# i2c_video_clock.net
KiCad netlist of a schematic drawn in Altium Designer
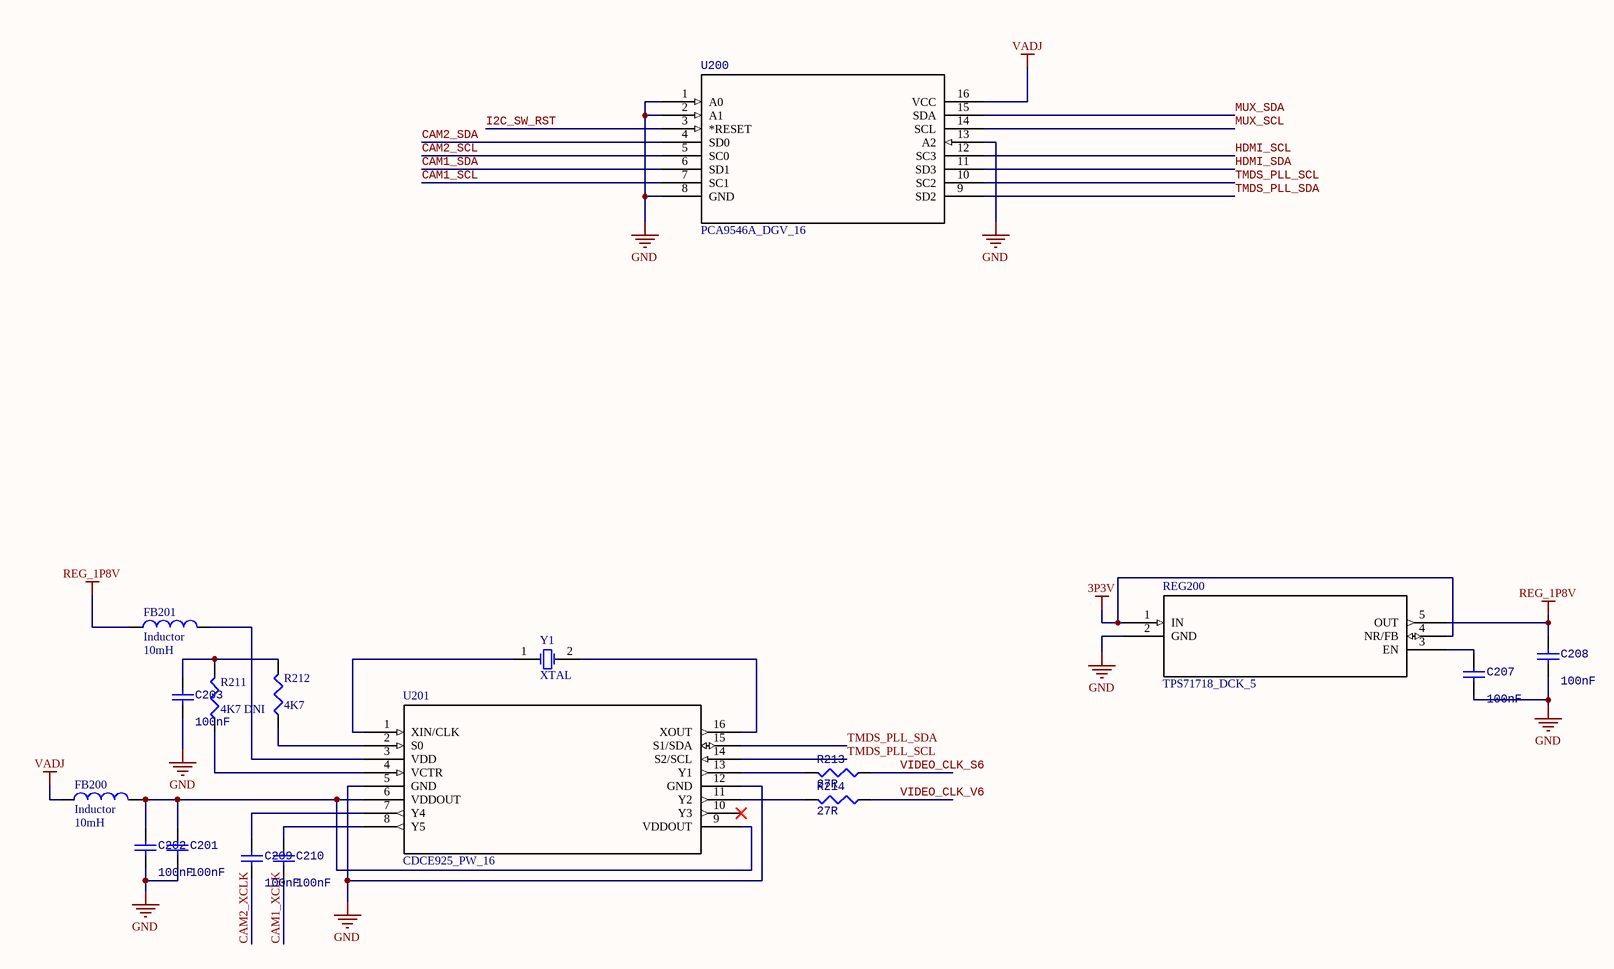
[diagram p0: i2c_video_clock.SchDoc]

(export (version "E")
  (design (tool "Eeschema 10.0.6"))
  (components
    (comp (ref "C201")
      (value "100nF")
      (footprint "1608[0603]")
      (description "Capacitor (Semiconductor SIM Model)")
      (fields (field (name "Comment") "Cap") (field (name "PUBLISHER") "Altium Limited"))
      (libsource (lib "Miscellaneous Devices") (part "Cap Semi"))
    )
    (comp (ref "C202")
      (value "100nF")
      (footprint "1608[0603]")
      (description "Capacitor (Semiconductor SIM Model)")
      (fields (field (name "Comment") "Cap") (field (name "PUBLISHER") "Altium Limited"))
      (libsource (lib "Miscellaneous Devices") (part "Cap Semi"))
    )
    (comp (ref "C203")
      (value "100nF")
      (footprint "1608[0603]")
      (description "Capacitor (Semiconductor SIM Model)")
      (fields (field (name "Comment") "Cap") (field (name "PUBLISHER") "Altium Limited"))
      (libsource (lib "Miscellaneous Devices") (part "Cap Semi"))
    )
    (comp (ref "C207")
      (value "100nF")
      (footprint "1608[0603]")
      (description "Capacitor (Semiconductor SIM Model)")
      (fields (field (name "Comment") "Cap") (field (name "PUBLISHER") "Altium Limited"))
      (libsource (lib "Miscellaneous Devices") (part "Cap Semi"))
    )
    (comp (ref "C208")
      (value "100nF")
      (footprint "1608[0603]")
      (description "Capacitor (Semiconductor SIM Model)")
      (fields (field (name "Comment") "Cap") (field (name "PUBLISHER") "Altium Limited"))
      (libsource (lib "Miscellaneous Devices") (part "Cap Semi"))
    )
    (comp (ref "C209")
      (value "100nF")
      (footprint "1608[0603]")
      (description "Capacitor (Semiconductor SIM Model)")
      (fields (field (name "Comment") "Cap") (field (name "PUBLISHER") "Altium Limited"))
      (libsource (lib "Miscellaneous Devices") (part "Cap Semi"))
    )
    (comp (ref "C210")
      (value "100nF")
      (footprint "1608[0603]")
      (description "Capacitor (Semiconductor SIM Model)")
      (fields (field (name "Comment") "Cap") (field (name "PUBLISHER") "Altium Limited"))
      (libsource (lib "Miscellaneous Devices") (part "Cap Semi"))
    )
    (comp (ref "FB200")
      (value "Inductor")
      (footprint "0603")
      (fields (field (name "ALTIUM_VALUE") "10mH") (field (name "PUBLISHER") "Altium Limited"))
      (libsource (lib "Miscellaneous Devices") (part "Inductor"))
    )
    (comp (ref "FB201")
      (value "Inductor")
      (footprint "0603")
      (fields (field (name "ALTIUM_VALUE") "10mH") (field (name "PUBLISHER") "Altium Limited"))
      (libsource (lib "Miscellaneous Devices") (part "Inductor"))
    )
    (comp (ref "R211")
      (value "4K7 DNI")
      (footprint "J1-0603")
      (description "Resistor")
      (fields (field (name "Comment") "Res3") (field (name "PUBLISHER") "Altium Limited"))
      (libsource (lib "Miscellaneous Devices") (part "Res3"))
    )
    (comp (ref "R212")
      (value "4K7")
      (footprint "J1-0603")
      (description "Resistor")
      (fields (field (name "Comment") "Res3") (field (name "PUBLISHER") "Altium Limited"))
      (libsource (lib "Miscellaneous Devices") (part "Res3"))
    )
    (comp (ref "R213")
      (value "27R")
      (footprint "J1-0603")
      (description "Resistor")
      (fields (field (name "Comment") "Res3") (field (name "PUBLISHER") "Altium Limited"))
      (libsource (lib "Miscellaneous Devices") (part "Res3"))
    )
    (comp (ref "R214")
      (value "27R")
      (footprint "J1-0603")
      (description "Resistor")
      (fields (field (name "Comment") "Res3") (field (name "PUBLISHER") "Altium Limited"))
      (libsource (lib "Miscellaneous Devices") (part "Res3"))
    )
    (comp (ref "REG200")
      (value "TPS71718_DCK_5")
      (footprint "DCK5")
      (description "Imported")
      (fields
        (field (name "MANUFACTURER_PART_NUMBER") "tps71718_dck_5")
        (field (name "GENERIC_PART_NUMBER") "TPS71718")
      )
      (libsource (lib "TPS71718DCK") (part "TPS71718_DCK_5"))
    )
    (comp (ref "U200")
      (value "PCA9546A_DGV_16")
      (footprint "DGV16")
      (description "Imported")
      (fields
        (field (name "MANUFACTURER") "Texas Instruments")
        (field (name "GENERIC_PART_NUMBER") "PCA9546A")
      )
      (libsource (lib "PCA9546ADGV") (part "PCA9546A_DGV_16"))
    )
    (comp (ref "U201")
      (value "CDCE925_PW_16")
      (footprint "PW16")
      (description "Imported")
      (fields
        (field (name "MANUFACTURER") "Texas Instruments")
        (field (name "GENERIC_PART_NUMBER") "CDCE925")
      )
      (libsource (lib "CDCE925PW") (part "CDCE925_PW_16"))
    )
    (comp (ref "Y1")
      (value "XTAL")
      (footprint "R38")
      (description "Crystal Oscillator")
      (fields (field (name "PUBLISHER") "Altium Limited"))
      (libsource (lib "Miscellaneous Devices") (part "XTAL"))
    )
  )
  (nets
    (net (code "1") (name "/CAM1_SCL") (class "Default")
      (node (ref "U200") (pin "7") (pinfunction "SC1_7") (pintype "passive"))
    )
    (net (code "2") (name "/CAM1_SDA") (class "Default")
      (node (ref "U200") (pin "6") (pinfunction "SD1_6") (pintype "passive"))
    )
    (net (code "3") (name "/CAM1_XCLK") (class "Default")
      (node (ref "C210") (pin "1") (pinfunction "1_1") (pintype "passive"))
    )
    (net (code "4") (name "/CAM2_SCL") (class "Default")
      (node (ref "U200") (pin "5") (pinfunction "SC0_5") (pintype "passive"))
    )
    (net (code "5") (name "/CAM2_SDA") (class "Default")
      (node (ref "U200") (pin "4") (pinfunction "SD0_4") (pintype "passive"))
    )
    (net (code "6") (name "/CAM2_XCLK") (class "Default")
      (node (ref "C209") (pin "1") (pinfunction "1_1") (pintype "passive"))
    )
    (net (code "7") (name "/HDMI_SCL") (class "Default")
      (node (ref "U200") (pin "12") (pinfunction "SC3_12") (pintype "passive"))
    )
    (net (code "8") (name "/HDMI_SDA") (class "Default")
      (node (ref "U200") (pin "11") (pinfunction "SD3_11") (pintype "passive"))
    )
    (net (code "9") (name "/I2C_SW_RST") (class "Default")
      (node (ref "U200") (pin "3") (pinfunction "*RESET_3") (pintype "input"))
    )
    (net (code "10") (name "/MUX_SCL") (class "Default")
      (node (ref "U200") (pin "14") (pinfunction "SCL_14") (pintype "passive"))
    )
    (net (code "11") (name "/MUX_SDA") (class "Default")
      (node (ref "U200") (pin "15") (pinfunction "SDA_15") (pintype "passive"))
    )
    (net (code "12") (name "/TMDS_PLL_SCL") (class "Default")
      (node (ref "U200") (pin "10") (pinfunction "SC2_10") (pintype "passive"))
      (node (ref "U201") (pin "14") (pinfunction "S2/SCL_14") (pintype "input"))
    )
    (net (code "13") (name "/TMDS_PLL_SDA") (class "Default")
      (node (ref "U200") (pin "9") (pinfunction "SD2_9") (pintype "passive"))
      (node (ref "U201") (pin "15") (pinfunction "S1/SDA_15") (pintype "bidirectional"))
    )
    (net (code "14") (name "/VIDEO_CLK_S6") (class "Default")
      (node (ref "R213") (pin "1") (pinfunction "1_1") (pintype "passive"))
    )
    (net (code "15") (name "/VIDEO_CLK_V6") (class "Default")
      (node (ref "R214") (pin "1") (pinfunction "1_1") (pintype "passive"))
    )
    (net (code "16") (name "3P3V") (class "Default")
      (node (ref "REG200") (pin "1") (pinfunction "IN_1") (pintype "input"))
      (node (ref "REG200") (pin "4") (pinfunction "NR/FB_4") (pintype "bidirectional"))
    )
    (net (code "17") (name "GND") (class "Default")
      (node (ref "C201") (pin "1") (pinfunction "1_1") (pintype "passive"))
      (node (ref "C202") (pin "1") (pinfunction "1_1") (pintype "passive"))
      (node (ref "C203") (pin "1") (pinfunction "1_1") (pintype "passive"))
      (node (ref "C207") (pin "1") (pinfunction "1_1") (pintype "passive"))
      (node (ref "C208") (pin "1") (pinfunction "1_1") (pintype "passive"))
      (node (ref "REG200") (pin "2") (pinfunction "GND_2") (pintype "power_in"))
      (node (ref "U200") (pin "1") (pinfunction "A0_1") (pintype "input"))
      (node (ref "U200") (pin "13") (pinfunction "A2_13") (pintype "input"))
      (node (ref "U200") (pin "2") (pinfunction "A1_2") (pintype "input"))
      (node (ref "U200") (pin "8") (pinfunction "GND_8") (pintype "power_in"))
      (node (ref "U201") (pin "12") (pinfunction "GND_12") (pintype "power_in"))
      (node (ref "U201") (pin "5") (pinfunction "GND_5") (pintype "power_in"))
    )
    (net (code "18") (name "Net-(C201-Pad2)") (class "Default")
      (node (ref "C201") (pin "2") (pinfunction "2_2") (pintype "passive"))
      (node (ref "C202") (pin "2") (pinfunction "2_2") (pintype "passive"))
      (node (ref "FB200") (pin "2") (pinfunction "2_2") (pintype "passive"))
      (node (ref "U201") (pin "6") (pinfunction "VDDOUT_6") (pintype "power_in"))
      (node (ref "U201") (pin "9") (pinfunction "VDDOUT_9") (pintype "power_in"))
    )
    (net (code "19") (name "Net-(C203-Pad2)") (class "Default")
      (node (ref "C203") (pin "2") (pinfunction "2_2") (pintype "passive"))
      (node (ref "R211") (pin "2") (pinfunction "2_2") (pintype "passive"))
      (node (ref "R212") (pin "2") (pinfunction "2_2") (pintype "passive"))
    )
    (net (code "20") (name "Net-(REG200-EN)") (class "Default")
      (node (ref "C207") (pin "2") (pinfunction "2_2") (pintype "passive"))
      (node (ref "REG200") (pin "3") (pinfunction "EN_3") (pintype "passive"))
    )
    (net (code "21") (name "Net-(U201-S0)") (class "Default")
      (node (ref "R212") (pin "1") (pinfunction "1_1") (pintype "passive"))
      (node (ref "U201") (pin "2") (pinfunction "S0_2") (pintype "input"))
    )
    (net (code "22") (name "Net-(U201-VCTR)") (class "Default")
      (node (ref "R211") (pin "1") (pinfunction "1_1") (pintype "passive"))
      (node (ref "U201") (pin "4") (pinfunction "VCTR_4") (pintype "input"))
    )
    (net (code "23") (name "Net-(U201-VDD)") (class "Default")
      (node (ref "FB201") (pin "2") (pinfunction "2_2") (pintype "passive"))
      (node (ref "U201") (pin "3") (pinfunction "VDD_3") (pintype "power_in"))
    )
    (net (code "24") (name "Net-(U201-XIN{slash}CLK)") (class "Default")
      (node (ref "U201") (pin "1") (pinfunction "XIN/CLK_1") (pintype "input"))
      (node (ref "Y1") (pin "1") (pinfunction "OSC1_1") (pintype "passive"))
    )
    (net (code "25") (name "Net-(U201-XOUT)") (class "Default")
      (node (ref "U201") (pin "16") (pinfunction "XOUT_16") (pintype "output"))
      (node (ref "Y1") (pin "2") (pinfunction "OSC2_2") (pintype "passive"))
    )
    (net (code "26") (name "Net-(U201-Y1)") (class "Default")
      (node (ref "R213") (pin "2") (pinfunction "2_2") (pintype "passive"))
      (node (ref "U201") (pin "13") (pinfunction "Y1_13") (pintype "output"))
    )
    (net (code "27") (name "Net-(U201-Y2)") (class "Default")
      (node (ref "R214") (pin "2") (pinfunction "2_2") (pintype "passive"))
      (node (ref "U201") (pin "11") (pinfunction "Y2_11") (pintype "output"))
    )
    (net (code "28") (name "Net-(U201-Y4)") (class "Default")
      (node (ref "C209") (pin "2") (pinfunction "2_2") (pintype "passive"))
      (node (ref "U201") (pin "7") (pinfunction "Y4_7") (pintype "output"))
    )
    (net (code "29") (name "Net-(U201-Y5)") (class "Default")
      (node (ref "C210") (pin "2") (pinfunction "2_2") (pintype "passive"))
      (node (ref "U201") (pin "8") (pinfunction "Y5_8") (pintype "output"))
    )
    (net (code "30") (name "REG_1P8V") (class "Default")
      (node (ref "C208") (pin "2") (pinfunction "2_2") (pintype "passive"))
      (node (ref "FB201") (pin "1") (pinfunction "1_1") (pintype "passive"))
      (node (ref "REG200") (pin "5") (pinfunction "OUT_5") (pintype "output"))
    )
    (net (code "31") (name "VADJ") (class "Default")
      (node (ref "FB200") (pin "1") (pinfunction "1_1") (pintype "passive"))
      (node (ref "U200") (pin "16") (pinfunction "VCC_16") (pintype "power_in"))
    )
    (net (code "32") (name "unconnected-(U201-Y3-Pad10)") (class "Default")
      (node (ref "U201") (pin "10") (pinfunction "Y3_10") (pintype "output+no_connect"))
    )
  )
)
